# LED.net
KiCad netlist of a schematic drawn in Altium Designer
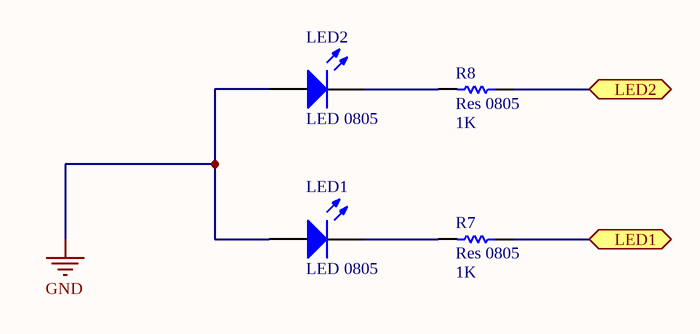
[diagram p0: LED.SchDoc]

(export (version "E")
  (design (tool "Eeschema 10.0.6"))
  (components
    (comp (ref "LED1")
      (value "LED 0805")
      (footprint "0805_A")
      (description "LED")
      (fields (field (name "MANUFACTURER") "Wuerth Elektronik") (field (name "PARTNUMBER") "150080SS75000"))
      (libsource (lib "Altium Content Vault") (part "WE-LED_K1A2-2"))
    )
    (comp (ref "LED2")
      (value "LED 0805")
      (footprint "0805_A")
      (description "LED")
      (fields (field (name "MANUFACTURER") "Wuerth Elektronik") (field (name "PARTNUMBER") "150080SS75000"))
      (libsource (lib "Altium Content Vault") (part "WE-LED_K1A2-2"))
    )
    (comp (ref "R7")
      (value "Res 0805")
      (footprint "RESC2013X50X30LL20T20")
      (description "Resistor")
      (fields (field (name "ALTIUM_VALUE") "1K"))
      (libsource (lib "Altium Content Vault") (part "RES"))
    )
    (comp (ref "R8")
      (value "Res 0805")
      (footprint "RESC2013X50X30LL20T20")
      (description "Resistor")
      (fields (field (name "ALTIUM_VALUE") "1K"))
      (libsource (lib "Altium Content Vault") (part "RES"))
    )
  )
  (nets
    (net (code "1") (name "/LED1") (class "Default")
      (node (ref "R7") (pin "1") (pinfunction "1_1") (pintype "passive"))
    )
    (net (code "2") (name "/LED2") (class "Default")
      (node (ref "R8") (pin "1") (pinfunction "1_1") (pintype "passive"))
    )
    (net (code "3") (name "GND") (class "Default")
      (node (ref "LED1") (pin "2") (pinfunction "A_2") (pintype "passive"))
      (node (ref "LED2") (pin "2") (pinfunction "A_2") (pintype "passive"))
    )
    (net (code "4") (name "Net-(LED1-K)") (class "Default")
      (node (ref "LED1") (pin "1") (pinfunction "K_1") (pintype "passive"))
      (node (ref "R7") (pin "2") (pinfunction "2_2") (pintype "passive"))
    )
    (net (code "5") (name "Net-(LED2-K)") (class "Default")
      (node (ref "LED2") (pin "1") (pinfunction "K_1") (pintype "passive"))
      (node (ref "R8") (pin "2") (pinfunction "2_2") (pintype "passive"))
    )
  )
)
